# ATTINY-V1.net
KiCad netlist of a schematic drawn in EAGLE
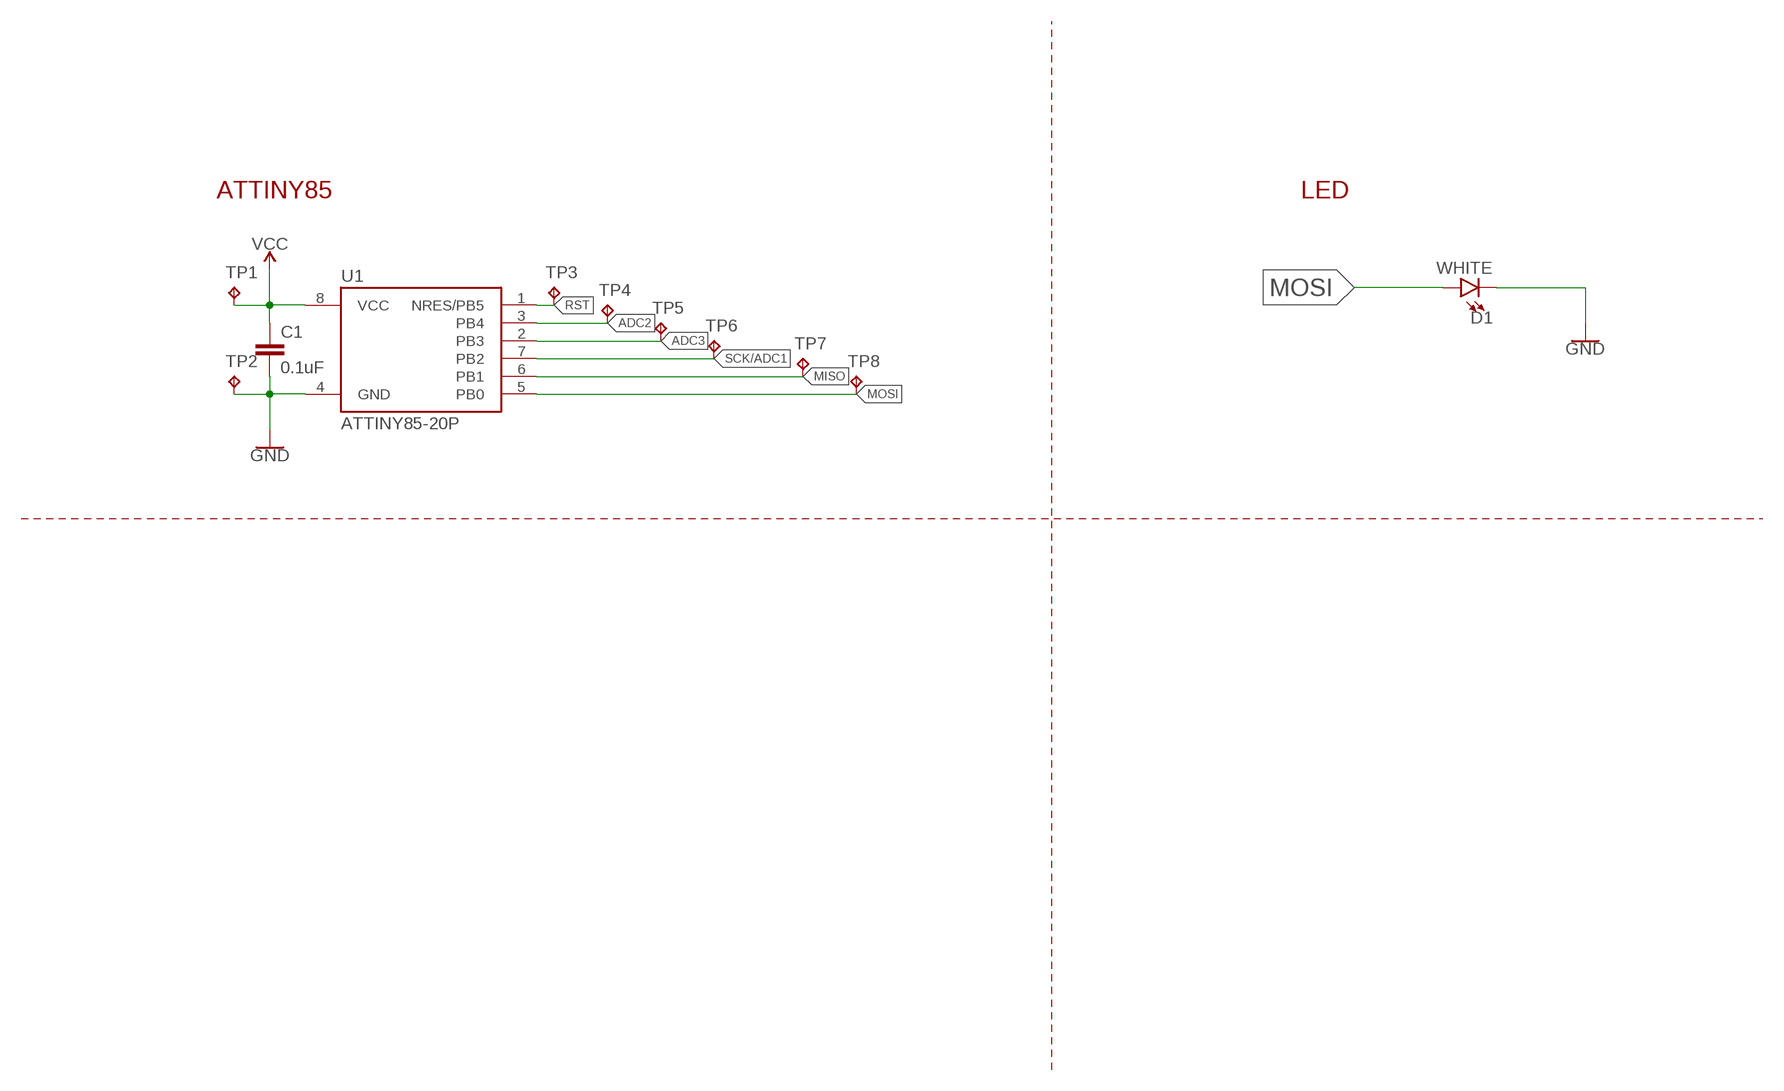
[diagram p0: schematic, sheet 1]

(export (version "E")
  (design (tool "Eeschema 10.0.6"))
  (components
    (comp (ref "C1")
      (value "0.1uF")
      (footprint "eagle-import:CAP-PTH-SMALL-KIT")
      (libsource (lib "eagle-import") (part "0.1UF-KIT-EZ-50V-20%"))
    )
    (comp (ref "D1")
      (value "WHITE")
      (footprint "eagle-import:LED-1206")
      (libsource (lib "eagle-import") (part "LED-WHITE1206"))
    )
    (comp (ref "TP1")
      (value "TPTP20R")
      (footprint "eagle-import:TP20R")
      (libsource (lib "eagle-import") (part "TPTP20R"))
    )
    (comp (ref "TP2")
      (value "TPTP20R")
      (footprint "eagle-import:TP20R")
      (libsource (lib "eagle-import") (part "TPTP20R"))
    )
    (comp (ref "TP3")
      (value "TPTP20R")
      (footprint "eagle-import:TP20R")
      (libsource (lib "eagle-import") (part "TPTP20R"))
    )
    (comp (ref "TP4")
      (value "TPTP20R")
      (footprint "eagle-import:TP20R")
      (libsource (lib "eagle-import") (part "TPTP20R"))
    )
    (comp (ref "TP5")
      (value "TPTP20R")
      (footprint "eagle-import:TP20R")
      (libsource (lib "eagle-import") (part "TPTP20R"))
    )
    (comp (ref "TP6")
      (value "TPTP20R")
      (footprint "eagle-import:TP20R")
      (libsource (lib "eagle-import") (part "TPTP20R"))
    )
    (comp (ref "TP7")
      (value "TPTP20R")
      (footprint "eagle-import:TP20R")
      (libsource (lib "eagle-import") (part "TPTP20R"))
    )
    (comp (ref "TP8")
      (value "TPTP20R")
      (footprint "eagle-import:TP20R")
      (libsource (lib "eagle-import") (part "TPTP20R"))
    )
    (comp (ref "U1")
      (value "ATTINY85-20P")
      (footprint "eagle-import:PDIP08_300MIL")
      (libsource (lib "eagle-import") (part "ATTINY85P-20"))
    )
  )
  (nets
    (net (code "1") (name "ADC2") (class "Default")
      (node (ref "TP4") (pin "TP") (pinfunction "TP_TP") (pintype "input"))
      (node (ref "U1") (pin "3") (pinfunction "PB4_3") (pintype "bidirectional"))
    )
    (net (code "2") (name "ADC3") (class "Default")
      (node (ref "TP5") (pin "TP") (pinfunction "TP_TP") (pintype "input"))
      (node (ref "U1") (pin "2") (pinfunction "PB3_2") (pintype "bidirectional"))
    )
    (net (code "3") (name "GND") (class "Default")
      (node (ref "C1") (pin "2") (pinfunction "2_2") (pintype "passive"))
      (node (ref "D1") (pin "C") (pinfunction "C_C") (pintype "passive"))
      (node (ref "TP2") (pin "TP") (pinfunction "TP_TP") (pintype "input"))
      (node (ref "U1") (pin "4") (pinfunction "GND_4") (pintype "power_in"))
    )
    (net (code "4") (name "MISO") (class "Default")
      (node (ref "TP7") (pin "TP") (pinfunction "TP_TP") (pintype "input"))
      (node (ref "U1") (pin "6") (pinfunction "PB1_6") (pintype "bidirectional"))
    )
    (net (code "5") (name "MOSI") (class "Default")
      (node (ref "D1") (pin "A") (pinfunction "A_A") (pintype "passive"))
      (node (ref "TP8") (pin "TP") (pinfunction "TP_TP") (pintype "input"))
      (node (ref "U1") (pin "5") (pinfunction "PB0_5") (pintype "bidirectional"))
    )
    (net (code "6") (name "RST") (class "Default")
      (node (ref "TP3") (pin "TP") (pinfunction "TP_TP") (pintype "input"))
      (node (ref "U1") (pin "1") (pinfunction "NRES/PB5_1") (pintype "bidirectional"))
    )
    (net (code "7") (name "SCK{slash}ADC1") (class "Default")
      (node (ref "TP6") (pin "TP") (pinfunction "TP_TP") (pintype "input"))
      (node (ref "U1") (pin "7") (pinfunction "PB2_7") (pintype "bidirectional"))
    )
    (net (code "8") (name "VCC") (class "Default")
      (node (ref "C1") (pin "1") (pinfunction "1_1") (pintype "passive"))
      (node (ref "TP1") (pin "TP") (pinfunction "TP_TP") (pintype "input"))
      (node (ref "U1") (pin "8") (pinfunction "VCC_8") (pintype "power_in"))
    )
  )
)
